# STM32.net
KiCad netlist of a schematic drawn in Altium Designer
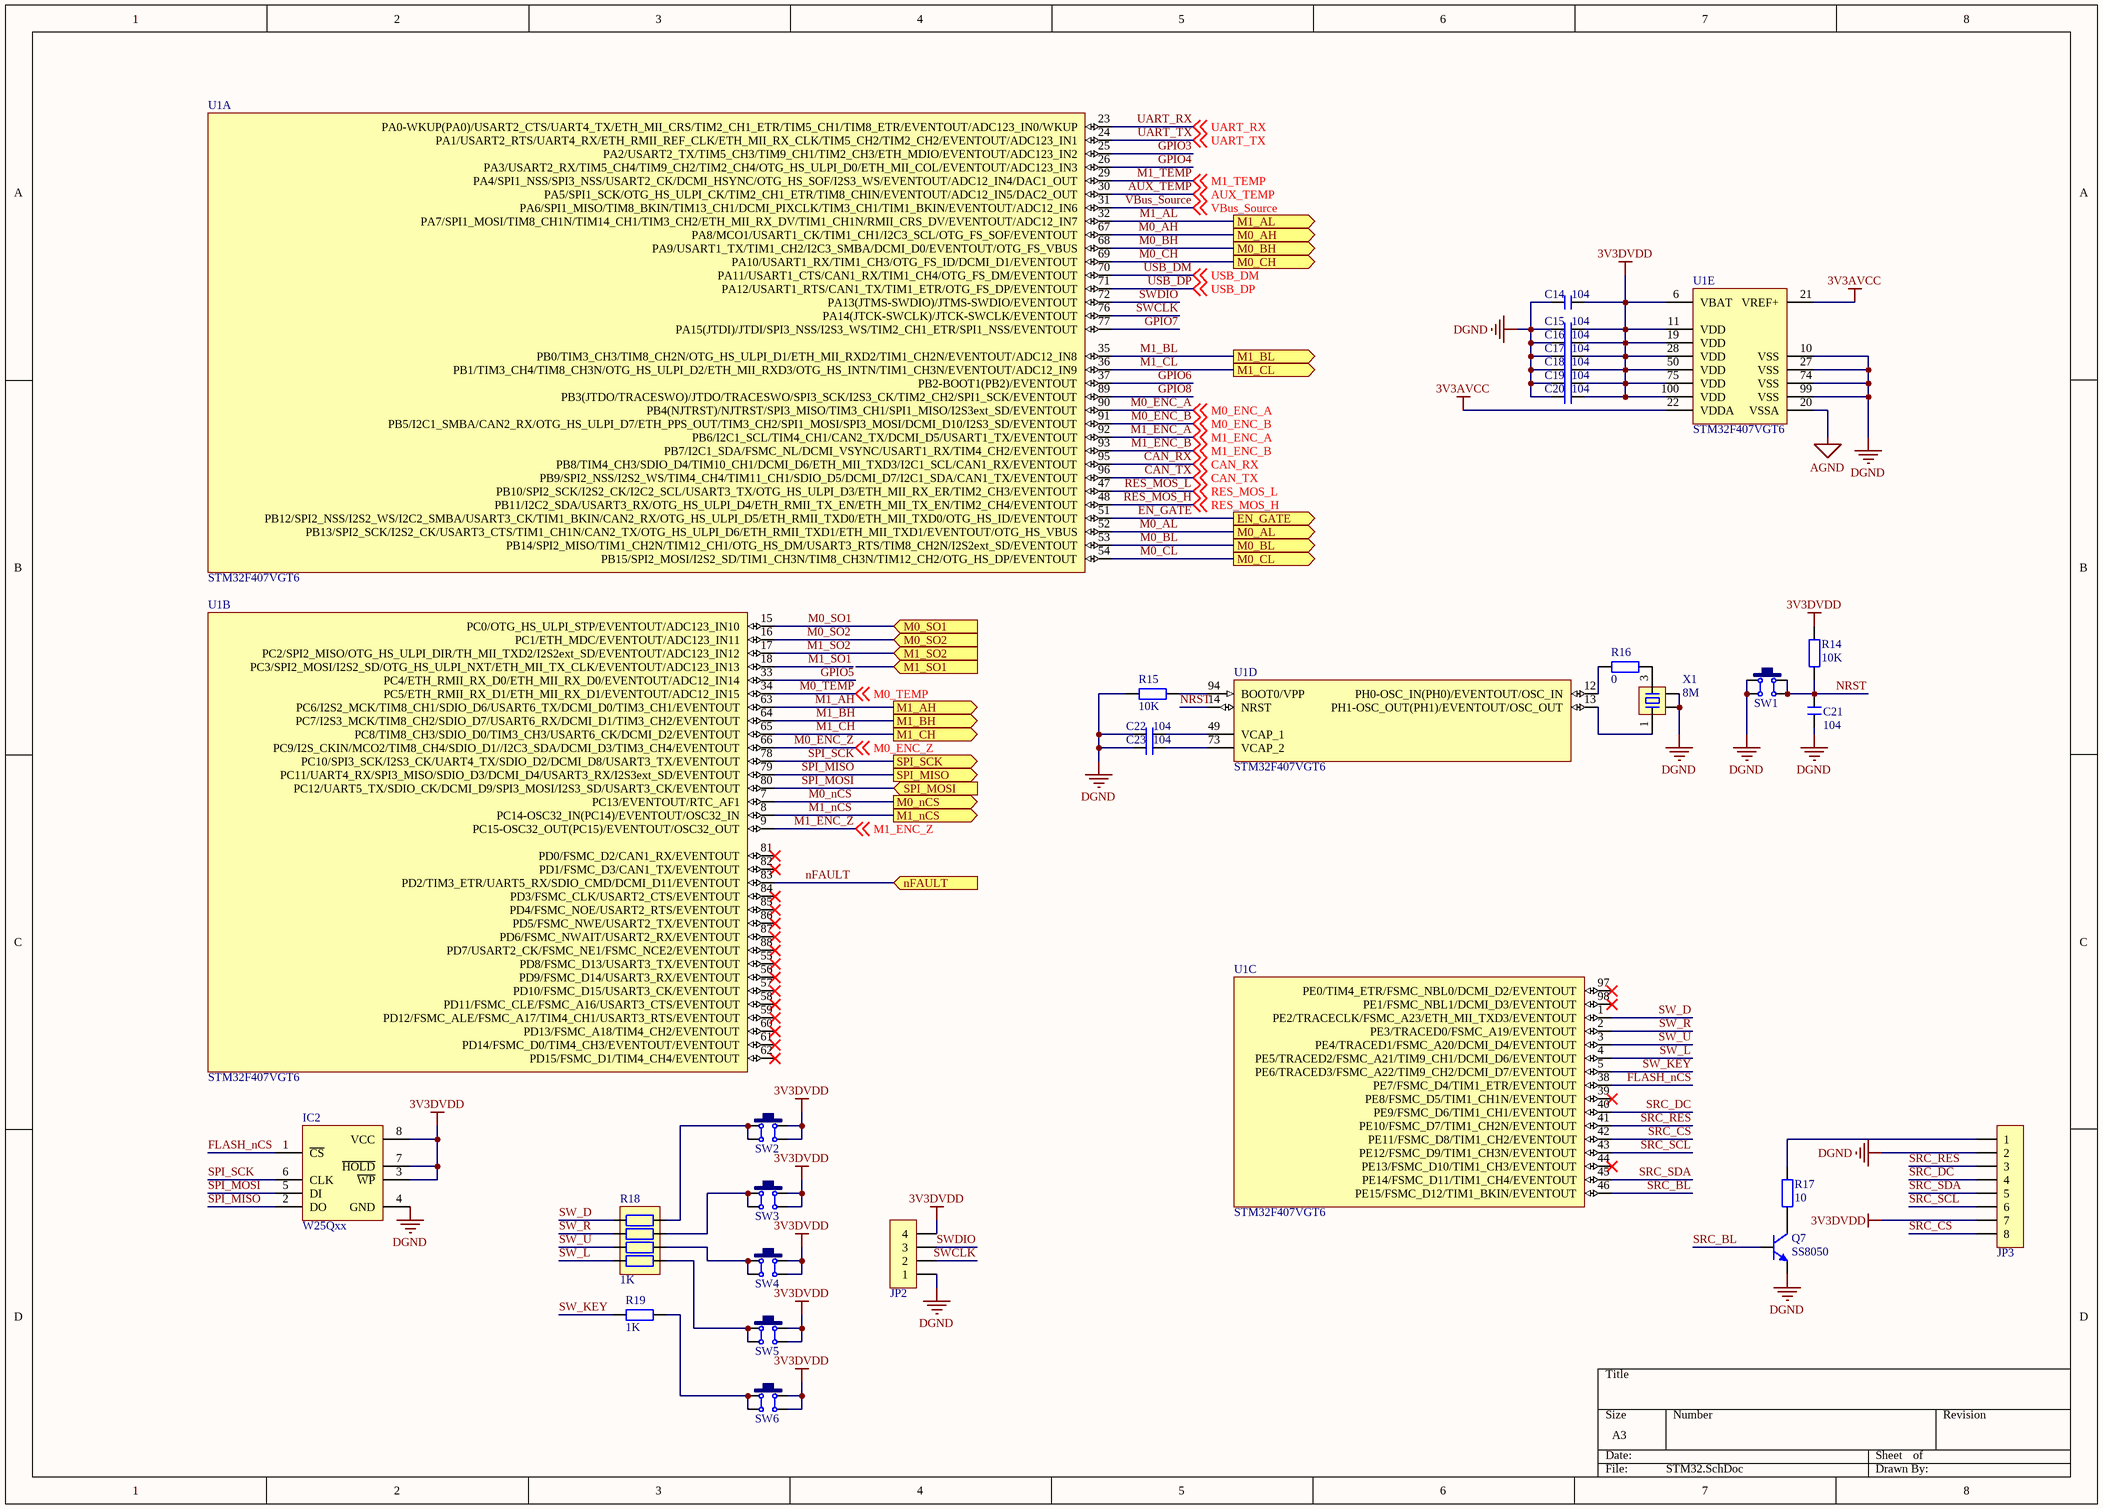
[diagram p0: STM32.SchDoc]

(export (version "E")
  (design (tool "Eeschema 10.0.6"))
  (components
    (comp (ref "C14")
      (value "104")
      (footprint "C 0603_L")
      (description "贴片电容")
      (libsource (lib "0.1 - 电阻-电容-电感") (part "C"))
    )
    (comp (ref "C15")
      (value "104")
      (footprint "C 0603_L")
      (description "贴片电容")
      (libsource (lib "0.1 - 电阻-电容-电感") (part "C"))
    )
    (comp (ref "C16")
      (value "104")
      (footprint "C 0603_L")
      (description "贴片电容")
      (libsource (lib "0.1 - 电阻-电容-电感") (part "C"))
    )
    (comp (ref "C17")
      (value "104")
      (footprint "C 0603_L")
      (description "贴片电容")
      (libsource (lib "0.1 - 电阻-电容-电感") (part "C"))
    )
    (comp (ref "C18")
      (value "104")
      (footprint "C 0603_L")
      (description "贴片电容")
      (libsource (lib "0.1 - 电阻-电容-电感") (part "C"))
    )
    (comp (ref "C19")
      (value "104")
      (footprint "C 0603_L")
      (description "贴片电容")
      (libsource (lib "0.1 - 电阻-电容-电感") (part "C"))
    )
    (comp (ref "C20")
      (value "104")
      (footprint "C 0603_L")
      (description "贴片电容")
      (libsource (lib "0.1 - 电阻-电容-电感") (part "C"))
    )
    (comp (ref "C21")
      (value "104")
      (footprint "C 0603_L")
      (description "贴片电容")
      (libsource (lib "0.1 - 电阻-电容-电感") (part "C"))
    )
    (comp (ref "C22")
      (value "104")
      (footprint "C 0603_L")
      (description "贴片电容")
      (libsource (lib "0.1 - 电阻-电容-电感") (part "C"))
    )
    (comp (ref "C23")
      (value "104")
      (footprint "C 0603_L")
      (description "贴片电容")
      (libsource (lib "0.1 - 电阻-电容-电感") (part "C"))
    )
    (comp (ref "IC2")
      (value "W25Qxx")
      (footprint "SOP8W_N")
      (description "SPI Flash")
      (fields (field (name "版权归属") "封装库来自淘宝 ID：黄晶宝石"))
      (libsource (lib "1.0 - 常见芯片") (part "W25Q"))
    )
    (comp (ref "JP2")
      (value "HDR-1X4")
      (footprint "HDR2.54-LI-4P")
      (description "4P接插件")
      (fields (field (name "版权归属") "封装库来自淘宝 ID：黄晶宝石"))
      (libsource (lib "5.3 - 接插件-脚距2.54 (100mil) ") (part "Header 4"))
    )
    (comp (ref "JP3")
      (value "HDR-1X8")
      (footprint "FPC0.5 2H-WS-8P")
      (description "8P接插件")
      (fields (field (name "版权归属") "封装库来自淘宝 ID：黄晶宝石"))
      (libsource (lib "5.0 - 接插件-脚距1.25") (part "Header 8"))
    )
    (comp (ref "Q7")
      (value "SS8050")
      (footprint "SOT23-3N")
      (description "高频放大-NPN型")
      (fields (field (name "版权归属") "封装库来自淘宝 ID：黄晶宝石"))
      (libsource (lib "0.4 - 三极管") (part "8050-SMD"))
    )
    (comp (ref "R14")
      (value "10K")
      (footprint "R 0603_L")
      (description "贴片电阻")
      (fields (field (name "版权归属") "来自淘宝 ID：黄晶宝石"))
      (libsource (lib "0.1 - 电阻-电容-电感") (part "R"))
    )
    (comp (ref "R15")
      (value "10K")
      (footprint "R 0603_L")
      (description "贴片电阻")
      (fields (field (name "版权归属") "来自淘宝 ID：黄晶宝石"))
      (libsource (lib "0.1 - 电阻-电容-电感") (part "R"))
    )
    (comp (ref "R16")
      (value "0")
      (footprint "R 0603_L")
      (description "贴片电阻")
      (fields (field (name "版权归属") "来自淘宝 ID：黄晶宝石"))
      (libsource (lib "0.1 - 电阻-电容-电感") (part "R"))
    )
    (comp (ref "R17")
      (value "10")
      (footprint "R 0603_L")
      (description "贴片电阻")
      (fields (field (name "版权归属") "来自淘宝 ID：黄晶宝石"))
      (libsource (lib "0.1 - 电阻-电容-电感") (part "R"))
    )
    (comp (ref "R18")
      (value "1K")
      (footprint "RCA-8P4R-0603")
      (description "贴片排阻")
      (fields (field (name "版权归属") "封装库来自淘宝 ID：黄晶宝石"))
      (libsource (lib "0.1 - 电阻-电容-电感") (part "R-8P4R"))
    )
    (comp (ref "R19")
      (value "1K")
      (footprint "R 0603_L")
      (description "贴片电阻")
      (fields (field (name "版权归属") "来自淘宝 ID：黄晶宝石"))
      (libsource (lib "0.1 - 电阻-电容-电感") (part "R"))
    )
    (comp (ref "SW1")
      (value "6x6x5")
      (footprint "TSW SMD-6*6*4.3")
      (description "贴片6x6轻触开关")
      (fields (field (name "版权归属") "封装库来自淘宝 ID：黄晶宝石"))
      (libsource (lib "0.7 - 常用按键-开关") (part "TSW SMD-6x6"))
    )
    (comp (ref "SW2")
      (value "6x6x5")
      (footprint "TSW SMD-6*6*4.3")
      (description "贴片6x6轻触开关")
      (fields (field (name "版权归属") "封装库来自淘宝 ID：黄晶宝石"))
      (libsource (lib "0.7 - 常用按键-开关") (part "TSW SMD-6x6"))
    )
    (comp (ref "SW3")
      (value "6x6x5")
      (footprint "TSW SMD-6*6*4.3")
      (description "贴片6x6轻触开关")
      (fields (field (name "版权归属") "封装库来自淘宝 ID：黄晶宝石"))
      (libsource (lib "0.7 - 常用按键-开关") (part "TSW SMD-6x6"))
    )
    (comp (ref "SW4")
      (value "6x6x5")
      (footprint "TSW SMD-6*6*4.3")
      (description "贴片6x6轻触开关")
      (fields (field (name "版权归属") "封装库来自淘宝 ID：黄晶宝石"))
      (libsource (lib "0.7 - 常用按键-开关") (part "TSW SMD-6x6"))
    )
    (comp (ref "SW5")
      (value "6x6x5")
      (footprint "TSW SMD-6*6*4.3")
      (description "贴片6x6轻触开关")
      (fields (field (name "版权归属") "封装库来自淘宝 ID：黄晶宝石"))
      (libsource (lib "0.7 - 常用按键-开关") (part "TSW SMD-6x6"))
    )
    (comp (ref "SW6")
      (value "6x6x5")
      (footprint "TSW SMD-6*6*4.3")
      (description "贴片6x6轻触开关")
      (fields (field (name "版权归属") "封装库来自淘宝 ID：黄晶宝石"))
      (libsource (lib "0.7 - 常用按键-开关") (part "TSW SMD-6x6"))
    )
    (comp (ref "U1")
      (value "STM32F407VGT6")
      (footprint "LQFP100_V")
      (libsource (lib "2.5 - STM32 F4系列MCU 集成库") (part "STM32F407VGT6"))
    )
    (comp (ref "X1")
      (value "8M")
      (footprint "OSC 3225-4P")
      (description "4脚无源晶振")
      (fields (field (name "版权归属") "封装库来自淘宝卖家 ID：黄晶宝石"))
      (libsource (lib "2.0 - 保险丝-晶振-光耦") (part "XTAL-4P"))
    )
  )
  (nets
    (net (code "1") (name "/EN_GATE") (class "Default")
      (node (ref "U1") (pin "51") (pinfunction "PB12/SPI2_NSS/I2S2_WS/I2C2_SMBA/USART3_CK/TIM1_BKIN/CAN2_RX/OTG_HS_ULPI_D5/ETH_RMII_TXD0/ETH_MII_TXD0/OTG_HS_ID/EVENTOUT_51") (pintype "bidirectional"))
    )
    (net (code "2") (name "/FLASH_nCS") (class "Default")
      (node (ref "IC2") (pin "1") (pinfunction "~{CS}_1") (pintype "passive"))
      (node (ref "U1") (pin "38") (pinfunction "PE7/FSMC_D4/TIM1_ETR/EVENTOUT_38") (pintype "bidirectional"))
    )
    (net (code "3") (name "/GPIO3") (class "Default")
      (node (ref "U1") (pin "25") (pinfunction "PA2/USART2_TX/TIM5_CH3/TIM9_CH1/TIM2_CH3/ETH_MDIO/EVENTOUT/ADC123_IN2_25") (pintype "bidirectional"))
    )
    (net (code "4") (name "/GPIO4") (class "Default")
      (node (ref "U1") (pin "26") (pinfunction "PA3/USART2_RX/TIM5_CH4/TIM9_CH2/TIM2_CH4/OTG_HS_ULPI_D0/ETH_MII_COL/EVENTOUT/ADC123_IN3_26") (pintype "bidirectional"))
    )
    (net (code "5") (name "/GPIO5") (class "Default")
      (node (ref "U1") (pin "33") (pinfunction "PC4/ETH_RMII_RX_D0/ETH_MII_RX_D0/EVENTOUT/ADC12_IN14_33") (pintype "bidirectional"))
    )
    (net (code "6") (name "/GPIO6") (class "Default")
      (node (ref "U1") (pin "37") (pinfunction "PB2-BOOT1(PB2)/EVENTOUT_37") (pintype "bidirectional"))
    )
    (net (code "7") (name "/GPIO7") (class "Default")
      (node (ref "U1") (pin "77") (pinfunction "PA15(JTDI)/JTDI/SPI3_NSS/I2S3_WS/TIM2_CH1_ETR/SPI1_NSS/EVENTOUT_77") (pintype "bidirectional"))
    )
    (net (code "8") (name "/GPIO8") (class "Default")
      (node (ref "U1") (pin "89") (pinfunction "PB3(JTDO/TRACESWO)/JTDO/TRACESWO/SPI3_SCK/I2S3_CK/TIM2_CH2/SPI1_SCK/EVENTOUT_89") (pintype "bidirectional"))
    )
    (net (code "9") (name "/M0_AH") (class "Default")
      (node (ref "U1") (pin "67") (pinfunction "PA8/MCO1/USART1_CK/TIM1_CH1/I2C3_SCL/OTG_FS_SOF/EVENTOUT_67") (pintype "bidirectional"))
    )
    (net (code "10") (name "/M0_AL") (class "Default")
      (node (ref "U1") (pin "52") (pinfunction "PB13/SPI2_SCK/I2S2_CK/USART3_CTS/TIM1_CH1N/CAN2_TX/OTG_HS_ULPI_D6/ETH_RMII_TXD1/ETH_MII_TXD1/EVENTOUT/OTG_HS_VBUS_52") (pintype "bidirectional"))
    )
    (net (code "11") (name "/M0_BH") (class "Default")
      (node (ref "U1") (pin "68") (pinfunction "PA9/USART1_TX/TIM1_CH2/I2C3_SMBA/DCMI_D0/EVENTOUT/OTG_FS_VBUS_68") (pintype "bidirectional"))
    )
    (net (code "12") (name "/M0_BL") (class "Default")
      (node (ref "U1") (pin "53") (pinfunction "PB14/SPI2_MISO/TIM1_CH2N/TIM12_CH1/OTG_HS_DM/USART3_RTS/TIM8_CH2N/I2S2ext_SD/EVENTOUT_53") (pintype "bidirectional"))
    )
    (net (code "13") (name "/M0_CH") (class "Default")
      (node (ref "U1") (pin "69") (pinfunction "PA10/USART1_RX/TIM1_CH3/OTG_FS_ID/DCMI_D1/EVENTOUT_69") (pintype "bidirectional"))
    )
    (net (code "14") (name "/M0_CL") (class "Default")
      (node (ref "U1") (pin "54") (pinfunction "PB15/SPI2_MOSI/I2S2_SD/TIM1_CH3N/TIM8_CH3N/TIM12_CH2/OTG_HS_DP/EVENTOUT_54") (pintype "bidirectional"))
    )
    (net (code "15") (name "/M0_SO1") (class "Default")
      (node (ref "U1") (pin "15") (pinfunction "PC0/OTG_HS_ULPI_STP/EVENTOUT/ADC123_IN10_15") (pintype "bidirectional"))
    )
    (net (code "16") (name "/M0_SO2") (class "Default")
      (node (ref "U1") (pin "16") (pinfunction "PC1/ETH_MDC/EVENTOUT/ADC123_IN11_16") (pintype "bidirectional"))
    )
    (net (code "17") (name "/M0_nCS") (class "Default")
      (node (ref "U1") (pin "7") (pinfunction "PC13/EVENTOUT/RTC_AF1_7") (pintype "bidirectional"))
    )
    (net (code "18") (name "/M1_AH") (class "Default")
      (node (ref "U1") (pin "63") (pinfunction "PC6/I2S2_MCK/TIM8_CH1/SDIO_D6/USART6_TX/DCMI_D0/TIM3_CH1/EVENTOUT_63") (pintype "bidirectional"))
    )
    (net (code "19") (name "/M1_AL") (class "Default")
      (node (ref "U1") (pin "32") (pinfunction "PA7/SPI1_MOSI/TIM8_CH1N/TIM14_CH1/TIM3_CH2/ETH_MII_RX_DV/TIM1_CH1N/RMII_CRS_DV/EVENTOUT/ADC12_IN7_32") (pintype "bidirectional"))
    )
    (net (code "20") (name "/M1_BH") (class "Default")
      (node (ref "U1") (pin "64") (pinfunction "PC7/I2S3_MCK/TIM8_CH2/SDIO_D7/USART6_RX/DCMI_D1/TIM3_CH2/EVENTOUT_64") (pintype "bidirectional"))
    )
    (net (code "21") (name "/M1_BL") (class "Default")
      (node (ref "U1") (pin "35") (pinfunction "PB0/TIM3_CH3/TIM8_CH2N/OTG_HS_ULPI_D1/ETH_MII_RXD2/TIM1_CH2N/EVENTOUT/ADC12_IN8_35") (pintype "bidirectional"))
    )
    (net (code "22") (name "/M1_CH") (class "Default")
      (node (ref "U1") (pin "65") (pinfunction "PC8/TIM8_CH3/SDIO_D0/TIM3_CH3/USART6_CK/DCMI_D2/EVENTOUT_65") (pintype "bidirectional"))
    )
    (net (code "23") (name "/M1_CL") (class "Default")
      (node (ref "U1") (pin "36") (pinfunction "PB1/TIM3_CH4/TIM8_CH3N/OTG_HS_ULPI_D2/ETH_MII_RXD3/OTG_HS_INTN/TIM1_CH3N/EVENTOUT/ADC12_IN9_36") (pintype "bidirectional"))
    )
    (net (code "24") (name "/M1_SO1") (class "Default")
      (node (ref "U1") (pin "18") (pinfunction "PC3/SPI2_MOSI/I2S2_SD/OTG_HS_ULPI_NXT/ETH_MII_TX_CLK/EVENTOUT/ADC123_IN13_18") (pintype "bidirectional"))
    )
    (net (code "25") (name "/M1_SO2") (class "Default")
      (node (ref "U1") (pin "17") (pinfunction "PC2/SPI2_MISO/OTG_HS_ULPI_DIR/TH_MII_TXD2/I2S2ext_SD/EVENTOUT/ADC123_IN12_17") (pintype "bidirectional"))
    )
    (net (code "26") (name "/M1_nCS") (class "Default")
      (node (ref "U1") (pin "8") (pinfunction "PC14-OSC32_IN(PC14)/EVENTOUT/OSC32_IN_8") (pintype "bidirectional"))
    )
    (net (code "27") (name "/NRST") (class "Default")
      (node (ref "C21") (pin "2") (pinfunction "2_2") (pintype "passive"))
      (node (ref "R14") (pin "1") (pinfunction "1_1") (pintype "passive"))
      (node (ref "SW1") (pin "2") (pinfunction "2_2") (pintype "passive"))
      (node (ref "SW1") (pin "3") (pinfunction "3_3") (pintype "passive"))
      (node (ref "U1") (pin "14") (pinfunction "NRST_14") (pintype "bidirectional"))
    )
    (net (code "28") (name "/SPI_MISO") (class "Default")
      (node (ref "IC2") (pin "2") (pinfunction "DO_2") (pintype "passive"))
      (node (ref "U1") (pin "79") (pinfunction "PC11/UART4_RX/SPI3_MISO/SDIO_D3/DCMI_D4/USART3_RX/I2S3ext_SD/EVENTOUT_79") (pintype "bidirectional"))
    )
    (net (code "29") (name "/SPI_MOSI") (class "Default")
      (node (ref "IC2") (pin "5") (pinfunction "DI_5") (pintype "passive"))
      (node (ref "U1") (pin "80") (pinfunction "PC12/UART5_TX/SDIO_CK/DCMI_D9/SPI3_MOSI/I2S3_SD/USART3_CK/EVENTOUT_80") (pintype "bidirectional"))
    )
    (net (code "30") (name "/SPI_SCK") (class "Default")
      (node (ref "IC2") (pin "6") (pinfunction "CLK_6") (pintype "passive"))
      (node (ref "U1") (pin "78") (pinfunction "PC10/SPI3_SCK/I2S3_CK/UART4_TX/SDIO_D2/DCMI_D8/USART3_TX/EVENTOUT_78") (pintype "bidirectional"))
    )
    (net (code "31") (name "/SRC_BL") (class "Default")
      (node (ref "Q7") (pin "1") (pinfunction "B_1") (pintype "passive"))
      (node (ref "U1") (pin "46") (pinfunction "PE15/FSMC_D12/TIM1_BKIN/EVENTOUT_46") (pintype "bidirectional"))
    )
    (net (code "32") (name "/SRC_CS") (class "Default")
      (node (ref "JP3") (pin "8") (pinfunction "8_8") (pintype "passive"))
      (node (ref "U1") (pin "42") (pinfunction "PE11/FSMC_D8/TIM1_CH2/EVENTOUT_42") (pintype "bidirectional"))
    )
    (net (code "33") (name "/SRC_DC") (class "Default")
      (node (ref "JP3") (pin "4") (pinfunction "4_4") (pintype "passive"))
      (node (ref "U1") (pin "40") (pinfunction "PE9/FSMC_D6/TIM1_CH1/EVENTOUT_40") (pintype "bidirectional"))
    )
    (net (code "34") (name "/SRC_RES") (class "Default")
      (node (ref "JP3") (pin "3") (pinfunction "3_3") (pintype "passive"))
      (node (ref "U1") (pin "41") (pinfunction "PE10/FSMC_D7/TIM1_CH2N/EVENTOUT_41") (pintype "bidirectional"))
    )
    (net (code "35") (name "/SRC_SCL") (class "Default")
      (node (ref "JP3") (pin "6") (pinfunction "6_6") (pintype "passive"))
      (node (ref "U1") (pin "43") (pinfunction "PE12/FSMC_D9/TIM1_CH3N/EVENTOUT_43") (pintype "bidirectional"))
    )
    (net (code "36") (name "/SRC_SDA") (class "Default")
      (node (ref "JP3") (pin "5") (pinfunction "5_5") (pintype "passive"))
      (node (ref "U1") (pin "45") (pinfunction "PE14/FSMC_D11/TIM1_CH4/EVENTOUT_45") (pintype "bidirectional"))
    )
    (net (code "37") (name "/SWCLK") (class "Default")
      (node (ref "JP2") (pin "2") (pinfunction "2_2") (pintype "passive"))
      (node (ref "U1") (pin "76") (pinfunction "PA14(JTCK-SWCLK)/JTCK-SWCLK/EVENTOUT_76") (pintype "bidirectional"))
    )
    (net (code "38") (name "/SWDIO") (class "Default")
      (node (ref "JP2") (pin "3") (pinfunction "3_3") (pintype "passive"))
      (node (ref "U1") (pin "72") (pinfunction "PA13(JTMS-SWDIO)/JTMS-SWDIO/EVENTOUT_72") (pintype "bidirectional"))
    )
    (net (code "39") (name "/SW_D") (class "Default")
      (node (ref "R18") (pin "1") (pinfunction "1_1") (pintype "passive"))
      (node (ref "U1") (pin "1") (pinfunction "PE2/TRACECLK/FSMC_A23/ETH_MII_TXD3/EVENTOUT_1") (pintype "bidirectional"))
    )
    (net (code "40") (name "/SW_KEY") (class "Default")
      (node (ref "R19") (pin "2") (pinfunction "2_2") (pintype "passive"))
      (node (ref "U1") (pin "5") (pinfunction "PE6/TRACED3/FSMC_A22/TIM9_CH2/DCMI_D7/EVENTOUT_5") (pintype "bidirectional"))
    )
    (net (code "41") (name "/SW_L") (class "Default")
      (node (ref "R18") (pin "4") (pinfunction "4_4") (pintype "passive"))
      (node (ref "U1") (pin "4") (pinfunction "PE5/TRACED2/FSMC_A21/TIM9_CH1/DCMI_D6/EVENTOUT_4") (pintype "bidirectional"))
    )
    (net (code "42") (name "/SW_R") (class "Default")
      (node (ref "R18") (pin "2") (pinfunction "2_2") (pintype "passive"))
      (node (ref "U1") (pin "2") (pinfunction "PE3/TRACED0/FSMC_A19/EVENTOUT_2") (pintype "bidirectional"))
    )
    (net (code "43") (name "/SW_U") (class "Default")
      (node (ref "R18") (pin "3") (pinfunction "3_3") (pintype "passive"))
      (node (ref "U1") (pin "3") (pinfunction "PE4/TRACED1/FSMC_A20/DCMI_D4/EVENTOUT_3") (pintype "bidirectional"))
    )
    (net (code "44") (name "/nFAULT") (class "Default")
      (node (ref "U1") (pin "83") (pinfunction "PD2/TIM3_ETR/UART5_RX/SDIO_CMD/DCMI_D11/EVENTOUT_83") (pintype "bidirectional"))
    )
    (net (code "45") (name "3V3AVCC") (class "Default")
      (node (ref "U1") (pin "21") (pinfunction "VREF+_21") (pintype "power_in"))
      (node (ref "U1") (pin "22") (pinfunction "VDDA_22") (pintype "power_in"))
    )
    (net (code "46") (name "3V3DVDD") (class "Default")
      (node (ref "C14") (pin "2") (pinfunction "2_2") (pintype "passive"))
      (node (ref "C15") (pin "2") (pinfunction "2_2") (pintype "passive"))
      (node (ref "C16") (pin "2") (pinfunction "2_2") (pintype "passive"))
      (node (ref "C17") (pin "2") (pinfunction "2_2") (pintype "passive"))
      (node (ref "C18") (pin "2") (pinfunction "2_2") (pintype "passive"))
      (node (ref "C19") (pin "2") (pinfunction "2_2") (pintype "passive"))
      (node (ref "C20") (pin "2") (pinfunction "2_2") (pintype "passive"))
      (node (ref "IC2") (pin "3") (pinfunction "~{WP}_3") (pintype "passive"))
      (node (ref "IC2") (pin "7") (pinfunction "~{HOLD}_7") (pintype "passive"))
      (node (ref "IC2") (pin "8") (pinfunction "VCC_8") (pintype "passive"))
      (node (ref "JP2") (pin "4") (pinfunction "4_4") (pintype "passive"))
      (node (ref "JP3") (pin "7") (pinfunction "7_7") (pintype "passive"))
      (node (ref "R14") (pin "2") (pinfunction "2_2") (pintype "passive"))
      (node (ref "SW2") (pin "2") (pinfunction "2_2") (pintype "passive"))
      (node (ref "SW2") (pin "3") (pinfunction "3_3") (pintype "passive"))
      (node (ref "SW3") (pin "2") (pinfunction "2_2") (pintype "passive"))
      (node (ref "SW3") (pin "3") (pinfunction "3_3") (pintype "passive"))
      (node (ref "SW4") (pin "2") (pinfunction "2_2") (pintype "passive"))
      (node (ref "SW4") (pin "3") (pinfunction "3_3") (pintype "passive"))
      (node (ref "SW5") (pin "2") (pinfunction "2_2") (pintype "passive"))
      (node (ref "SW5") (pin "3") (pinfunction "3_3") (pintype "passive"))
      (node (ref "SW6") (pin "2") (pinfunction "2_2") (pintype "passive"))
      (node (ref "SW6") (pin "3") (pinfunction "3_3") (pintype "passive"))
      (node (ref "U1") (pin "100") (pinfunction "VDD_100") (pintype "power_in"))
      (node (ref "U1") (pin "11") (pinfunction "VDD_11") (pintype "power_in"))
      (node (ref "U1") (pin "19") (pinfunction "VDD_19") (pintype "power_in"))
      (node (ref "U1") (pin "28") (pinfunction "VDD_28") (pintype "power_in"))
      (node (ref "U1") (pin "50") (pinfunction "VDD_50") (pintype "power_in"))
      (node (ref "U1") (pin "6") (pinfunction "VBAT_6") (pintype "power_in"))
      (node (ref "U1") (pin "75") (pinfunction "VDD_75") (pintype "power_in"))
    )
    (net (code "47") (name "AGND") (class "Default")
      (node (ref "U1") (pin "20") (pinfunction "VSSA_20") (pintype "power_in"))
    )
    (net (code "48") (name "AUX_TEMP") (class "Default")
      (node (ref "U1") (pin "30") (pinfunction "PA5/SPI1_SCK/OTG_HS_ULPI_CK/TIM2_CH1_ETR/TIM8_CHIN/EVENTOUT/ADC12_IN5/DAC2_OUT_30") (pintype "bidirectional"))
    )
    (net (code "49") (name "CAN_RX") (class "Default")
      (node (ref "U1") (pin "95") (pinfunction "PB8/TIM4_CH3/SDIO_D4/TIM10_CH1/DCMI_D6/ETH_MII_TXD3/I2C1_SCL/CAN1_RX/EVENTOUT_95") (pintype "bidirectional"))
    )
    (net (code "50") (name "CAN_TX") (class "Default")
      (node (ref "U1") (pin "96") (pinfunction "PB9/SPI2_NSS/I2S2_WS/TIM4_CH4/TIM11_CH1/SDIO_D5/DCMI_D7/I2C1_SDA/CAN1_TX/EVENTOUT_96") (pintype "bidirectional"))
    )
    (net (code "51") (name "DGND") (class "Default")
      (node (ref "C14") (pin "1") (pinfunction "1_1") (pintype "passive"))
      (node (ref "C15") (pin "1") (pinfunction "1_1") (pintype "passive"))
      (node (ref "C16") (pin "1") (pinfunction "1_1") (pintype "passive"))
      (node (ref "C17") (pin "1") (pinfunction "1_1") (pintype "passive"))
      (node (ref "C18") (pin "1") (pinfunction "1_1") (pintype "passive"))
      (node (ref "C19") (pin "1") (pinfunction "1_1") (pintype "passive"))
      (node (ref "C20") (pin "1") (pinfunction "1_1") (pintype "passive"))
      (node (ref "C21") (pin "1") (pinfunction "1_1") (pintype "passive"))
      (node (ref "C22") (pin "1") (pinfunction "1_1") (pintype "passive"))
      (node (ref "C23") (pin "1") (pinfunction "1_1") (pintype "passive"))
      (node (ref "IC2") (pin "4") (pinfunction "GND_4") (pintype "passive"))
      (node (ref "JP2") (pin "1") (pinfunction "1_1") (pintype "passive"))
      (node (ref "JP3") (pin "2") (pinfunction "2_2") (pintype "passive"))
      (node (ref "Q7") (pin "2") (pinfunction "E_2") (pintype "passive"))
      (node (ref "R15") (pin "1") (pinfunction "1_1") (pintype "passive"))
      (node (ref "SW1") (pin "1") (pinfunction "1_1") (pintype "passive"))
      (node (ref "SW1") (pin "4") (pinfunction "4_4") (pintype "passive"))
      (node (ref "U1") (pin "10") (pinfunction "VSS_10") (pintype "power_in"))
      (node (ref "U1") (pin "27") (pinfunction "VSS_27") (pintype "power_in"))
      (node (ref "U1") (pin "74") (pinfunction "VSS_74") (pintype "power_in"))
      (node (ref "U1") (pin "99") (pinfunction "VSS_99") (pintype "power_in"))
      (node (ref "X1") (pin "2") (pinfunction "2_2") (pintype "passive"))
      (node (ref "X1") (pin "4") (pinfunction "4_4") (pintype "passive"))
    )
    (net (code "52") (name "M0_ENC_A") (class "Default")
      (node (ref "U1") (pin "90") (pinfunction "PB4(NJTRST)/NJTRST/SPI3_MISO/TIM3_CH1/SPI1_MISO/I2S3ext_SD/EVENTOUT_90") (pintype "bidirectional"))
    )
    (net (code "53") (name "M0_ENC_B") (class "Default")
      (node (ref "U1") (pin "91") (pinfunction "PB5/I2C1_SMBA/CAN2_RX/OTG_HS_ULPI_D7/ETH_PPS_OUT/TIM3_CH2/SPI1_MOSI/SPI3_MOSI/DCMI_D10/I2S3_SD/EVENTOUT_91") (pintype "bidirectional"))
    )
    (net (code "54") (name "M0_ENC_Z") (class "Default")
      (node (ref "U1") (pin "66") (pinfunction "PC9/I2S_CKIN/MCO2/TIM8_CH4/SDIO_D1//I2C3_SDA/DCMI_D3/TIM3_CH4/EVENTOUT_66") (pintype "bidirectional"))
    )
    (net (code "55") (name "M0_TEMP") (class "Default")
      (node (ref "U1") (pin "34") (pinfunction "PC5/ETH_RMII_RX_D1/ETH_MII_RX_D1/EVENTOUT/ADC12_IN15_34") (pintype "bidirectional"))
    )
    (net (code "56") (name "M1_ENC_A") (class "Default")
      (node (ref "U1") (pin "92") (pinfunction "PB6/I2C1_SCL/TIM4_CH1/CAN2_TX/DCMI_D5/USART1_TX/EVENTOUT_92") (pintype "bidirectional"))
    )
    (net (code "57") (name "M1_ENC_B") (class "Default")
      (node (ref "U1") (pin "93") (pinfunction "PB7/I2C1_SDA/FSMC_NL/DCMI_VSYNC/USART1_RX/TIM4_CH2/EVENTOUT_93") (pintype "bidirectional"))
    )
    (net (code "58") (name "M1_ENC_Z") (class "Default")
      (node (ref "U1") (pin "9") (pinfunction "PC15-OSC32_OUT(PC15)/EVENTOUT/OSC32_OUT_9") (pintype "bidirectional"))
    )
    (net (code "59") (name "M1_TEMP") (class "Default")
      (node (ref "U1") (pin "29") (pinfunction "PA4/SPI1_NSS/SPI3_NSS/USART2_CK/DCMI_HSYNC/OTG_HS_SOF/I2S3_WS/EVENTOUT/ADC12_IN4/DAC1_OUT_29") (pintype "bidirectional"))
    )
    (net (code "60") (name "Net-(JP3-Pad1)") (class "Default")
      (node (ref "JP3") (pin "1") (pinfunction "1_1") (pintype "passive"))
      (node (ref "R17") (pin "2") (pinfunction "2_2") (pintype "passive"))
    )
    (net (code "61") (name "Net-(Q7-C)") (class "Default")
      (node (ref "Q7") (pin "3") (pinfunction "C_3") (pintype "passive"))
      (node (ref "R17") (pin "1") (pinfunction "1_1") (pintype "passive"))
    )
    (net (code "62") (name "Net-(R16-Pad1)") (class "Default")
      (node (ref "R16") (pin "1") (pinfunction "1_1") (pintype "passive"))
      (node (ref "X1") (pin "3") (pinfunction "3_3") (pintype "passive"))
    )
    (net (code "63") (name "Net-(R18-Pad5)") (class "Default")
      (node (ref "R18") (pin "5") (pinfunction "5_5") (pintype "passive"))
      (node (ref "SW5") (pin "1") (pinfunction "1_1") (pintype "passive"))
      (node (ref "SW5") (pin "4") (pinfunction "4_4") (pintype "passive"))
    )
    (net (code "64") (name "Net-(R18-Pad6)") (class "Default")
      (node (ref "R18") (pin "6") (pinfunction "6_6") (pintype "passive"))
      (node (ref "SW4") (pin "1") (pinfunction "1_1") (pintype "passive"))
      (node (ref "SW4") (pin "4") (pinfunction "4_4") (pintype "passive"))
    )
    (net (code "65") (name "Net-(R18-Pad7)") (class "Default")
      (node (ref "R18") (pin "7") (pinfunction "7_7") (pintype "passive"))
      (node (ref "SW3") (pin "1") (pinfunction "1_1") (pintype "passive"))
      (node (ref "SW3") (pin "4") (pinfunction "4_4") (pintype "passive"))
    )
    (net (code "66") (name "Net-(R18-Pad8)") (class "Default")
      (node (ref "R18") (pin "8") (pinfunction "8_8") (pintype "passive"))
      (node (ref "SW2") (pin "1") (pinfunction "1_1") (pintype "passive"))
      (node (ref "SW2") (pin "4") (pinfunction "4_4") (pintype "passive"))
    )
    (net (code "67") (name "Net-(R19-Pad1)") (class "Default")
      (node (ref "R19") (pin "1") (pinfunction "1_1") (pintype "passive"))
      (node (ref "SW6") (pin "1") (pinfunction "1_1") (pintype "passive"))
      (node (ref "SW6") (pin "4") (pinfunction "4_4") (pintype "passive"))
    )
    (net (code "68") (name "Net-(U1D-BOOT0{slash}VPP)") (class "Default")
      (node (ref "R15") (pin "2") (pinfunction "2_2") (pintype "passive"))
      (node (ref "U1") (pin "94") (pinfunction "BOOT0/VPP_94") (pintype "input"))
    )
    (net (code "69") (name "Net-(U1D-PH0-OSC_IN(PH0){slash}EVENTOUT{slash}OSC_IN)") (class "Default")
      (node (ref "R16") (pin "2") (pinfunction "2_2") (pintype "passive"))
      (node (ref "U1") (pin "12") (pinfunction "PH0-OSC_IN(PH0)/EVENTOUT/OSC_IN_12") (pintype "bidirectional"))
    )
    (net (code "70") (name "Net-(U1D-PH1-OSC_OUT(PH1){slash}EVENTOUT{slash}OSC_OUT)") (class "Default")
      (node (ref "U1") (pin "13") (pinfunction "PH1-OSC_OUT(PH1)/EVENTOUT/OSC_OUT_13") (pintype "bidirectional"))
      (node (ref "X1") (pin "1") (pinfunction "1_1") (pintype "passive"))
    )
    (net (code "71") (name "Net-(U1D-VCAP_1)") (class "Default")
      (node (ref "C22") (pin "2") (pinfunction "2_2") (pintype "passive"))
      (node (ref "U1") (pin "49") (pinfunction "VCAP_1_49") (pintype "power_in"))
    )
    (net (code "72") (name "Net-(U1D-VCAP_2)") (class "Default")
      (node (ref "C23") (pin "2") (pinfunction "2_2") (pintype "passive"))
      (node (ref "U1") (pin "73") (pinfunction "VCAP_2_73") (pintype "power_in"))
    )
    (net (code "73") (name "RES_MOS_H") (class "Default")
      (node (ref "U1") (pin "48") (pinfunction "PB11/I2C2_SDA/USART3_RX/OTG_HS_ULPI_D4/ETH_RMII_TX_EN/ETH_MII_TX_EN/TIM2_CH4/EVENTOUT_48") (pintype "bidirectional"))
    )
    (net (code "74") (name "RES_MOS_L") (class "Default")
      (node (ref "U1") (pin "47") (pinfunction "PB10/SPI2_SCK/I2S2_CK/I2C2_SCL/USART3_TX/OTG_HS_ULPI_D3/ETH_MII_RX_ER/TIM2_CH3/EVENTOUT_47") (pintype "bidirectional"))
    )
    (net (code "75") (name "UART_RX") (class "Default")
      (node (ref "U1") (pin "23") (pinfunction "PA0-WKUP(PA0)/USART2_CTS/UART4_TX/ETH_MII_CRS/TIM2_CH1_ETR/TIM5_CH1/TIM8_ETR/EVENTOUT/ADC123_IN0/WKUP_23") (pintype "bidirectional"))
    )
    (net (code "76") (name "UART_TX") (class "Default")
      (node (ref "U1") (pin "24") (pinfunction "PA1/USART2_RTS/UART4_RX/ETH_RMII_REF_CLK/ETH_MII_RX_CLK/TIM5_CH2/TIM2_CH2/EVENTOUT/ADC123_IN1_24") (pintype "bidirectional"))
    )
    (net (code "77") (name "USB_DM") (class "Default")
      (node (ref "U1") (pin "70") (pinfunction "PA11/USART1_CTS/CAN1_RX/TIM1_CH4/OTG_FS_DM/EVENTOUT_70") (pintype "bidirectional"))
    )
    (net (code "78") (name "USB_DP") (class "Default")
      (node (ref "U1") (pin "71") (pinfunction "PA12/USART1_RTS/CAN1_TX/TIM1_ETR/OTG_FS_DP/EVENTOUT_71") (pintype "bidirectional"))
    )
    (net (code "79") (name "VBus_Source") (class "Default")
      (node (ref "U1") (pin "31") (pinfunction "PA6/SPI1_MISO/TIM8_BKIN/TIM13_CH1/DCMI_PIXCLK/TIM3_CH1/TIM1_BKIN/EVENTOUT/ADC12_IN6_31") (pintype "bidirectional"))
    )
    (net (code "80") (name "unconnected-(U1B-PD0{slash}FSMC_D2{slash}CAN1_RX{slash}EVENTOUT-Pad81)") (class "Default")
      (node (ref "U1") (pin "81") (pinfunction "PD0/FSMC_D2/CAN1_RX/EVENTOUT_81") (pintype "bidirectional+no_connect"))
    )
    (net (code "81") (name "unconnected-(U1B-PD1{slash}FSMC_D3{slash}CAN1_TX{slash}EVENTOUT-Pad82)") (class "Default")
      (node (ref "U1") (pin "82") (pinfunction "PD1/FSMC_D3/CAN1_TX/EVENTOUT_82") (pintype "bidirectional+no_connect"))
    )
    (net (code "82") (name "unconnected-(U1B-PD3{slash}FSMC_CLK{slash}USART2_CTS{slash}EVENTOUT-Pad84)") (class "Default")
      (node (ref "U1") (pin "84") (pinfunction "PD3/FSMC_CLK/USART2_CTS/EVENTOUT_84") (pintype "bidirectional+no_connect"))
    )
    (net (code "83") (name "unconnected-(U1B-PD4{slash}FSMC_NOE{slash}USART2_RTS{slash}EVENTOUT-Pad85)") (class "Default")
      (node (ref "U1") (pin "85") (pinfunction "PD4/FSMC_NOE/USART2_RTS/EVENTOUT_85") (pintype "bidirectional+no_connect"))
    )
    (net (code "84") (name "unconnected-(U1B-PD5{slash}FSMC_NWE{slash}USART2_TX{slash}EVENTOUT-Pad86)") (class "Default")
      (node (ref "U1") (pin "86") (pinfunction "PD5/FSMC_NWE/USART2_TX/EVENTOUT_86") (pintype "bidirectional+no_connect"))
    )
    (net (code "85") (name "unconnected-(U1B-PD6{slash}FSMC_NWAIT{slash}USART2_RX{slash}EVENTOUT-Pad87)") (class "Default")
      (node (ref "U1") (pin "87") (pinfunction "PD6/FSMC_NWAIT/USART2_RX/EVENTOUT_87") (pintype "bidirectional+no_connect"))
    )
    (net (code "86") (name "unconnected-(U1B-PD7{slash}USART2_CK{slash}FSMC_NE1{slash}FSMC_NCE2{slash}EVENTOUT-Pad88)") (class "Default")
      (node (ref "U1") (pin "88") (pinfunction "PD7/USART2_CK/FSMC_NE1/FSMC_NCE2/EVENTOUT_88") (pintype "bidirectional+no_connect"))
    )
    (net (code "87") (name "unconnected-(U1B-PD8{slash}FSMC_D13{slash}USART3_TX{slash}EVENTOUT-Pad55)") (class "Default")
      (node (ref "U1") (pin "55") (pinfunction "PD8/FSMC_D13/USART3_TX/EVENTOUT_55") (pintype "bidirectional+no_connect"))
    )
    (net (code "88") (name "unconnected-(U1B-PD9{slash}FSMC_D14{slash}USART3_RX{slash}EVENTOUT-Pad56)") (class "Default")
      (node (ref "U1") (pin "56") (pinfunction "PD9/FSMC_D14/USART3_RX/EVENTOUT_56") (pintype "bidirectional+no_connect"))
    )
    (net (code "89") (name "unconnected-(U1B-PD10{slash}FSMC_D15{slash}USART3_CK{slash}EVENTOUT-Pad57)") (class "Default")
      (node (ref "U1") (pin "57") (pinfunction "PD10/FSMC_D15/USART3_CK/EVENTOUT_57") (pintype "bidirectional+no_connect"))
    )
    (net (code "90") (name "unconnected-(U1B-PD11{slash}FSMC_CLE{slash}FSMC_A16{slash}USART3_CTS{slash}EVENTOUT-Pad58)") (class "Default")
      (node (ref "U1") (pin "58") (pinfunction "PD11/FSMC_CLE/FSMC_A16/USART3_CTS/EVENTOUT_58") (pintype "bidirectional+no_connect"))
    )
    (net (code "91") (name "unconnected-(U1B-PD12{slash}FSMC_ALE{slash}FSMC_A17{slash}TIM4_CH1{slash}USART3_RTS{slash}EVENTOUT-Pad59)") (class "Default")
      (node (ref "U1") (pin "59") (pinfunction "PD12/FSMC_ALE/FSMC_A17/TIM4_CH1/USART3_RTS/EVENTOUT_59") (pintype "bidirectional+no_connect"))
    )
    (net (code "92") (name "unconnected-(U1B-PD13{slash}FSMC_A18{slash}TIM4_CH2{slash}EVENTOUT-Pad60)") (class "Default")
      (node (ref "U1") (pin "60") (pinfunction "PD13/FSMC_A18/TIM4_CH2/EVENTOUT_60") (pintype "bidirectional+no_connect"))
    )
    (net (code "93") (name "unconnected-(U1B-PD14{slash}FSMC_D0{slash}TIM4_CH3{slash}EVENTOUT{slash}EVENTOUT-Pad61)") (class "Default")
      (node (ref "U1") (pin "61") (pinfunction "PD14/FSMC_D0/TIM4_CH3/EVENTOUT/EVENTOUT_61") (pintype "bidirectional+no_connect"))
    )
    (net (code "94") (name "unconnected-(U1B-PD15{slash}FSMC_D1{slash}TIM4_CH4{slash}EVENTOUT-Pad62)") (class "Default")
      (node (ref "U1") (pin "62") (pinfunction "PD15/FSMC_D1/TIM4_CH4/EVENTOUT_62") (pintype "bidirectional+no_connect"))
    )
    (net (code "95") (name "unconnected-(U1C-PE0{slash}TIM4_ETR{slash}FSMC_NBL0{slash}DCMI_D2{slash}EVENTOUT-Pad97)") (class "Default")
      (node (ref "U1") (pin "97") (pinfunction "PE0/TIM4_ETR/FSMC_NBL0/DCMI_D2/EVENTOUT_97") (pintype "bidirectional+no_connect"))
    )
    (net (code "96") (name "unconnected-(U1C-PE1{slash}FSMC_NBL1{slash}DCMI_D3{slash}EVENTOUT-Pad98)") (class "Default")
      (node (ref "U1") (pin "98") (pinfunction "PE1/FSMC_NBL1/DCMI_D3/EVENTOUT_98") (pintype "bidirectional+no_connect"))
    )
    (net (code "97") (name "unconnected-(U1C-PE8{slash}FSMC_D5{slash}TIM1_CH1N{slash}EVENTOUT-Pad39)") (class "Default")
      (node (ref "U1") (pin "39") (pinfunction "PE8/FSMC_D5/TIM1_CH1N/EVENTOUT_39") (pintype "bidirectional+no_connect"))
    )
    (net (code "98") (name "unconnected-(U1C-PE13{slash}FSMC_D10{slash}TIM1_CH3{slash}EVENTOUT-Pad44)") (class "Default")
      (node (ref "U1") (pin "44") (pinfunction "PE13/FSMC_D10/TIM1_CH3/EVENTOUT_44") (pintype "bidirectional+no_connect"))
    )
  )
)
